# 606_outin_ichigojam.net
KiCad netlist of a schematic drawn in EAGLE
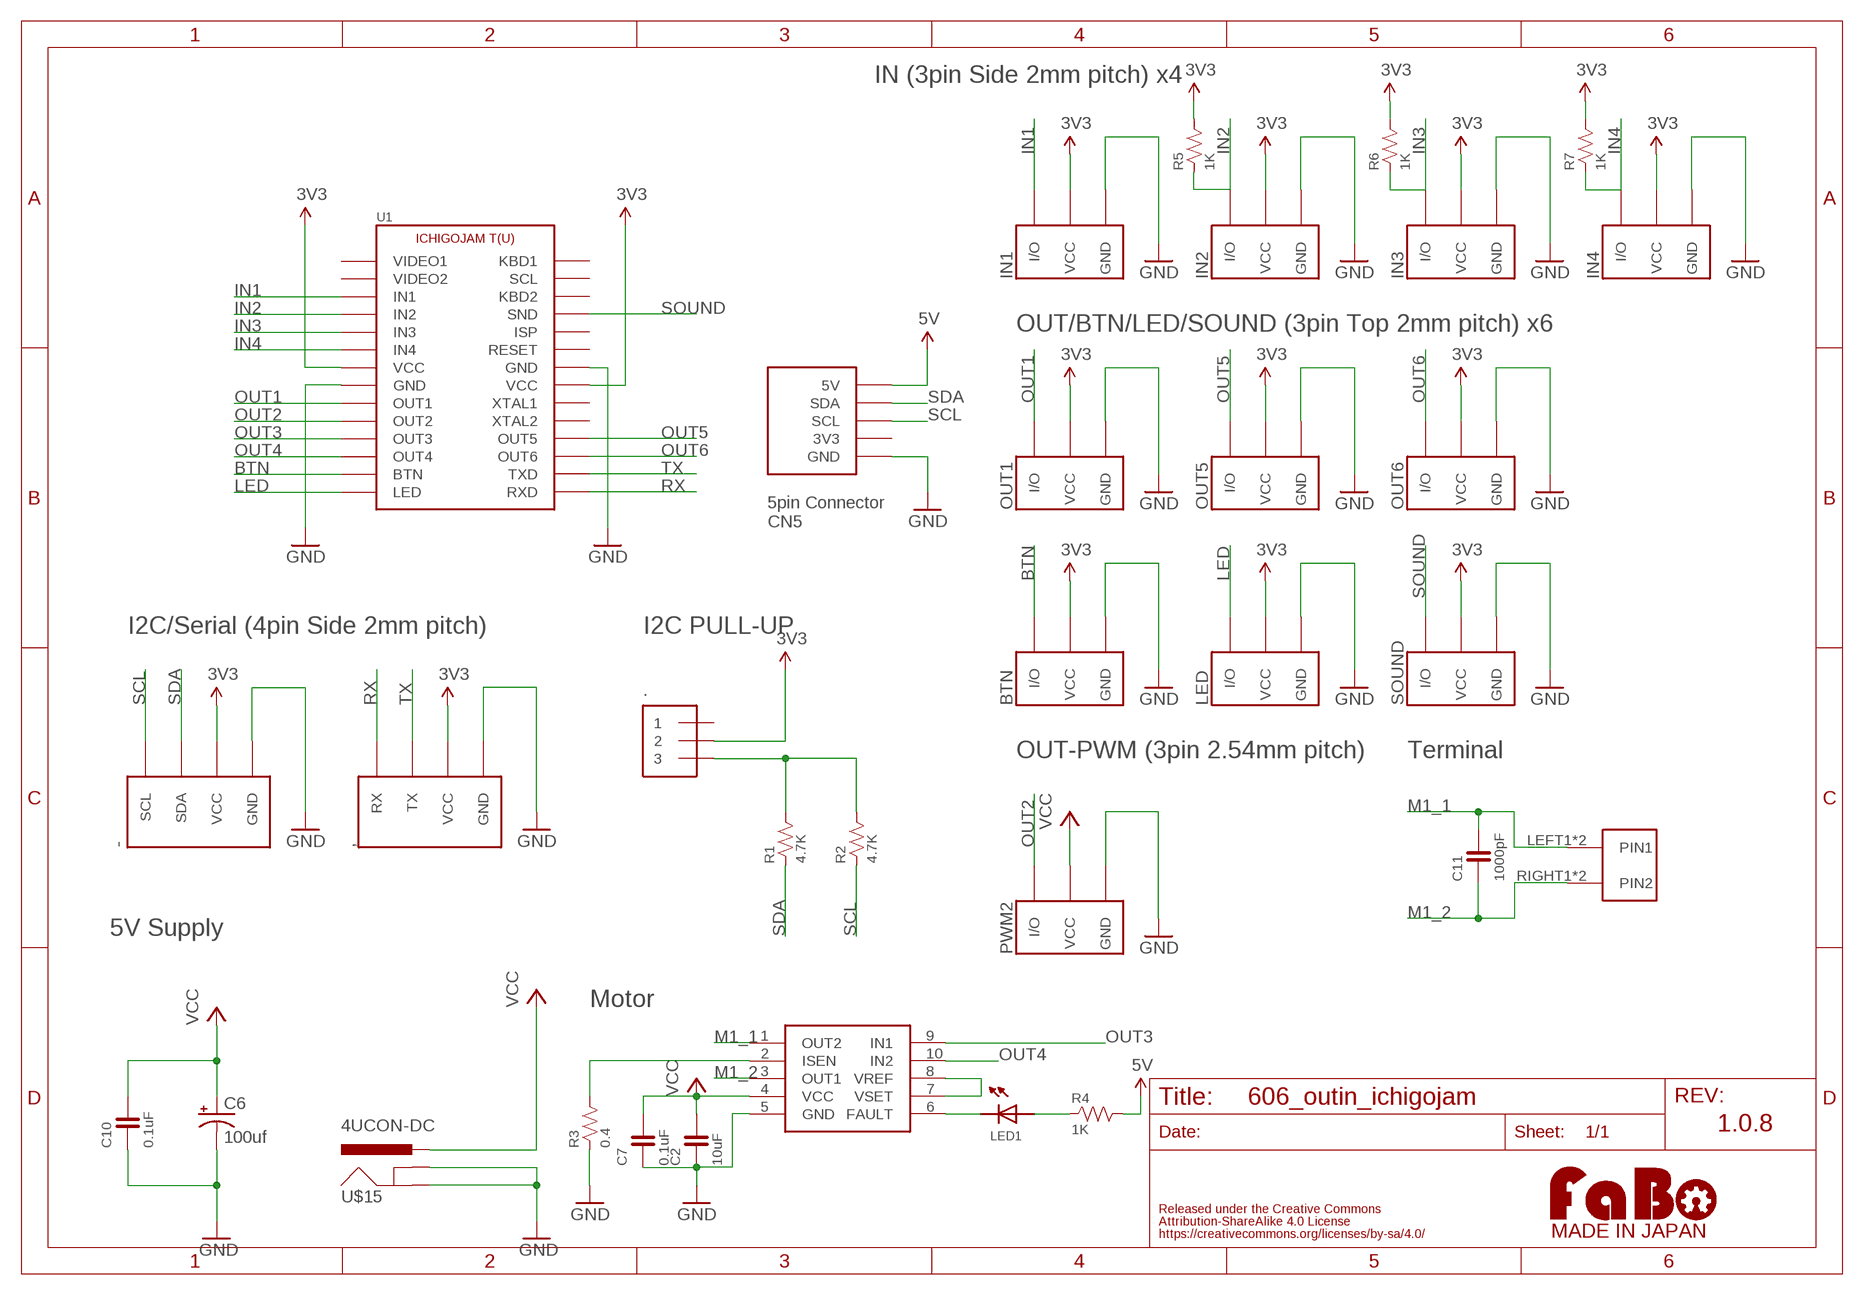
[diagram p0: schematic, sheet 1]

(export (version "E")
  (design (tool "Eeschema 10.0.6"))
  (components
    (comp (ref ",")
      (value "FABO_BRICK_SERIAL-S04B-PASK-2_LONG")
      (footprint "eagle-import:FABO_BRICK_SERIAL_S04B-PASK-2_LONG")
      (libsource (lib "eagle-import") (part "FABO_BRICK_SERIAL-S04B-PASK-2_LONG"))
    )
    (comp (ref "-")
      (value "FABO_BRICK_I2C-S04B-PASK-2_LONG")
      (footprint "eagle-import:FABO_BRICK_I2C_S04B-PASK-2_LONG")
      (libsource (lib "eagle-import") (part "FABO_BRICK_I2C-S04B-PASK-2_LONG"))
    )
    (comp (ref ".")
      (value "PIN_HEADER_1X3")
      (footprint "eagle-import:PIN_1X3")
      (libsource (lib "eagle-import") (part "PIN_HEADER_1X3"))
    )
    (comp (ref "BTN")
      (value "FABO_BRICK_3PIN-B03B-PASK-1")
      (footprint "eagle-import:FABO_BRICK_3PIN_B03B-PASK-1")
      (libsource (lib "eagle-import") (part "FABO_BRICK_3PIN-B03B-PASK-1"))
    )
    (comp (ref "C2")
      (value "10uF")
      (footprint "eagle-import:0603")
      (libsource (lib "eagle-import") (part "CAPACITOR-0603"))
    )
    (comp (ref "C6")
      (value "100uf")
      (footprint "eagle-import:153CLV-0405")
      (libsource (lib "eagle-import") (part "CPOL-US153CLV-0405"))
    )
    (comp (ref "C7")
      (value "0.1uF")
      (footprint "eagle-import:0603")
      (libsource (lib "eagle-import") (part "CAPACITOR-0603"))
    )
    (comp (ref "C10")
      (value "0.1uF")
      (footprint "eagle-import:0603")
      (libsource (lib "eagle-import") (part "CAPACITOR-0603"))
    )
    (comp (ref "C11")
      (value "1000pF")
      (footprint "eagle-import:0603")
      (libsource (lib "eagle-import") (part "CAPACITOR-0603"))
    )
    (comp (ref "IN1")
      (value "FABO_BRICK_3PIN-B03B-PASK-1")
      (footprint "eagle-import:FABO_BRICK_3PIN_B03B-PASK-1")
      (libsource (lib "eagle-import") (part "FABO_BRICK_3PIN-B03B-PASK-1"))
    )
    (comp (ref "IN2")
      (value "FABO_BRICK_3PIN-B03B-PASK-1")
      (footprint "eagle-import:FABO_BRICK_3PIN_B03B-PASK-1")
      (libsource (lib "eagle-import") (part "FABO_BRICK_3PIN-B03B-PASK-1"))
    )
    (comp (ref "IN3")
      (value "FABO_BRICK_3PIN-B03B-PASK-1")
      (footprint "eagle-import:FABO_BRICK_3PIN_B03B-PASK-1")
      (libsource (lib "eagle-import") (part "FABO_BRICK_3PIN-B03B-PASK-1"))
    )
    (comp (ref "IN4")
      (value "FABO_BRICK_3PIN-B03B-PASK-1")
      (footprint "eagle-import:FABO_BRICK_3PIN_B03B-PASK-1")
      (libsource (lib "eagle-import") (part "FABO_BRICK_3PIN-B03B-PASK-1"))
    )
    (comp (ref "LED")
      (value "FABO_BRICK_3PIN-B03B-PASK-1")
      (footprint "eagle-import:FABO_BRICK_3PIN_B03B-PASK-1")
      (libsource (lib "eagle-import") (part "FABO_BRICK_3PIN-B03B-PASK-1"))
    )
    (comp (ref "LED1")
      (value "LED-0603")
      (footprint "eagle-import:0603")
      (libsource (lib "eagle-import") (part "LED-0603"))
    )
    (comp (ref "OUT1")
      (value "FABO_BRICK_3PIN-B03B-PASK-1")
      (footprint "eagle-import:FABO_BRICK_3PIN_B03B-PASK-1")
      (libsource (lib "eagle-import") (part "FABO_BRICK_3PIN-B03B-PASK-1"))
    )
    (comp (ref "OUT5")
      (value "FABO_BRICK_3PIN-B03B-PASK-1")
      (footprint "eagle-import:FABO_BRICK_3PIN_B03B-PASK-1")
      (libsource (lib "eagle-import") (part "FABO_BRICK_3PIN-B03B-PASK-1"))
    )
    (comp (ref "OUT6")
      (value "FABO_BRICK_3PIN-B03B-PASK-1")
      (footprint "eagle-import:FABO_BRICK_3PIN_B03B-PASK-1")
      (libsource (lib "eagle-import") (part "FABO_BRICK_3PIN-B03B-PASK-1"))
    )
    (comp (ref "PWM2")
      (value "FABO_BRICK_3PIN-HEADER")
      (footprint "eagle-import:FABO_BRICK_3PIN_HEADER")
      (libsource (lib "eagle-import") (part "FABO_BRICK_3PIN-HEADER"))
    )
    (comp (ref "R1")
      (value "4.7K")
      (footprint "eagle-import:0603")
      (libsource (lib "eagle-import") (part "RESISTOR-0603"))
    )
    (comp (ref "R2")
      (value "4.7K")
      (footprint "eagle-import:0603")
      (libsource (lib "eagle-import") (part "RESISTOR-0603"))
    )
    (comp (ref "R3")
      (value "0.4")
      (footprint "eagle-import:0603")
      (libsource (lib "eagle-import") (part "RESISTOR-0603"))
    )
    (comp (ref "R4")
      (value "1K")
      (footprint "eagle-import:0603")
      (libsource (lib "eagle-import") (part "RESISTOR-0603"))
    )
    (comp (ref "R5")
      (value "1K")
      (footprint "eagle-import:0603")
      (libsource (lib "eagle-import") (part "RESISTOR-0603"))
    )
    (comp (ref "R6")
      (value "1K")
      (footprint "eagle-import:0603")
      (libsource (lib "eagle-import") (part "RESISTOR-0603"))
    )
    (comp (ref "R7")
      (value "1K")
      (footprint "eagle-import:0603")
      (libsource (lib "eagle-import") (part "RESISTOR-0603"))
    )
    (comp (ref "SOUND")
      (value "FABO_BRICK_3PIN-B03B-PASK-1")
      (footprint "eagle-import:FABO_BRICK_3PIN_B03B-PASK-1")
      (libsource (lib "eagle-import") (part "FABO_BRICK_3PIN-B03B-PASK-1"))
    )
    (comp (ref "U$3")
      (value "LOGO_FABO-M")
      (footprint "eagle-import:LOGO_FABO_MS")
      (libsource (lib "eagle-import") (part "LOGO_FABO-M"))
    )
    (comp (ref "U$6")
      (value "DRV8832")
      (footprint "eagle-import:DRV8830")
      (libsource (lib "eagle-import") (part "DRV8832"))
    )
    (comp (ref "U$12")
      (value "ML-1400-S1")
      (footprint "eagle-import:ML-1400-S1")
      (libsource (lib "eagle-import") (part "ML-1400-S1"))
    )
    (comp (ref "U$15")
      (value "4UCON-DC")
      (footprint "eagle-import:4UCON-DC")
      (libsource (lib "eagle-import") (part "4UCON-DC"))
    )
    (comp (ref "U1")
      (value "ICHIGOJAM_T-NOLABEL")
      (footprint "eagle-import:ICHIGOJAM_T_NOLABEL")
      (libsource (lib "eagle-import") (part "ICHIGOJAM_T-NOLABEL"))
    )
  )
  (nets
    (net (code "1") (name "/BTN") (class "Default")
      (node (ref "BTN") (pin "I/O") (pinfunction "I/O_I/O") (pintype "bidirectional"))
      (node (ref "U1") (pin "BTN") (pinfunction "BTN_BTN") (pintype "bidirectional"))
    )
    (net (code "2") (name "/IN1") (class "Default")
      (node (ref "IN1") (pin "I/O") (pinfunction "I/O_I/O") (pintype "bidirectional"))
      (node (ref "U1") (pin "IN1") (pinfunction "IN1_IN1") (pintype "bidirectional"))
    )
    (net (code "3") (name "/IN2") (class "Default")
      (node (ref "IN2") (pin "I/O") (pinfunction "I/O_I/O") (pintype "bidirectional"))
      (node (ref "R5") (pin "1") (pinfunction "1_1") (pintype "bidirectional"))
      (node (ref "U1") (pin "IN2") (pinfunction "IN2_IN2") (pintype "bidirectional"))
    )
    (net (code "4") (name "/IN3") (class "Default")
      (node (ref "IN3") (pin "I/O") (pinfunction "I/O_I/O") (pintype "bidirectional"))
      (node (ref "R6") (pin "1") (pinfunction "1_1") (pintype "bidirectional"))
      (node (ref "U1") (pin "IN3") (pinfunction "IN3_IN3") (pintype "bidirectional"))
    )
    (net (code "5") (name "/IN4") (class "Default")
      (node (ref "IN4") (pin "I/O") (pinfunction "I/O_I/O") (pintype "bidirectional"))
      (node (ref "R7") (pin "1") (pinfunction "1_1") (pintype "bidirectional"))
      (node (ref "U1") (pin "IN4") (pinfunction "IN4_IN4") (pintype "bidirectional"))
    )
    (net (code "6") (name "/LED") (class "Default")
      (node (ref "LED") (pin "I/O") (pinfunction "I/O_I/O") (pintype "bidirectional"))
      (node (ref "U1") (pin "LED") (pinfunction "LED_LED") (pintype "bidirectional"))
    )
    (net (code "7") (name "/M1_1") (class "Default")
      (node (ref "C11") (pin "2") (pinfunction "2_2") (pintype "passive"))
      (node (ref "U$12") (pin "LEFT1") (pinfunction "PIN1_LEFT1") (pintype "bidirectional"))
      (node (ref "U$12") (pin "LEFT2") (pinfunction "PIN1_LEFT2") (pintype "bidirectional"))
      (node (ref "U$6") (pin "1") (pinfunction "OUT2_1") (pintype "bidirectional"))
    )
    (net (code "8") (name "/M1_2") (class "Default")
      (node (ref "C11") (pin "1") (pinfunction "1_1") (pintype "passive"))
      (node (ref "U$12") (pin "RIGHT1") (pinfunction "PIN2_RIGHT1") (pintype "bidirectional"))
      (node (ref "U$12") (pin "RIGHT2") (pinfunction "PIN2_RIGHT2") (pintype "bidirectional"))
      (node (ref "U$6") (pin "3") (pinfunction "OUT1_3") (pintype "bidirectional"))
    )
    (net (code "9") (name "/OUT1") (class "Default")
      (node (ref "OUT1") (pin "I/O") (pinfunction "I/O_I/O") (pintype "bidirectional"))
      (node (ref "U1") (pin "OUT1") (pinfunction "OUT1_OUT1") (pintype "bidirectional"))
    )
    (net (code "10") (name "/OUT2") (class "Default")
      (node (ref "PWM2") (pin "I/O") (pinfunction "I/O_I/O") (pintype "bidirectional"))
      (node (ref "U1") (pin "OUT2") (pinfunction "OUT2_OUT2") (pintype "bidirectional"))
    )
    (net (code "11") (name "/OUT3") (class "Default")
      (node (ref "U$6") (pin "9") (pinfunction "IN1_9") (pintype "bidirectional"))
      (node (ref "U1") (pin "OUT3") (pinfunction "OUT3_OUT3") (pintype "bidirectional"))
    )
    (net (code "12") (name "/OUT4") (class "Default")
      (node (ref "U$6") (pin "10") (pinfunction "IN2_10") (pintype "bidirectional"))
      (node (ref "U1") (pin "OUT4") (pinfunction "OUT4_OUT4") (pintype "bidirectional"))
    )
    (net (code "13") (name "/OUT5") (class "Default")
      (node (ref "OUT5") (pin "I/O") (pinfunction "I/O_I/O") (pintype "bidirectional"))
      (node (ref "U1") (pin "OUT5") (pinfunction "OUT5_OUT5") (pintype "bidirectional"))
    )
    (net (code "14") (name "/OUT6") (class "Default")
      (node (ref "OUT6") (pin "I/O") (pinfunction "I/O_I/O") (pintype "bidirectional"))
      (node (ref "U1") (pin "OUT6") (pinfunction "OUT6_OUT6") (pintype "bidirectional"))
    )
    (net (code "15") (name "/RX") (class "Default")
      (node (ref ",") (pin "RX") (pinfunction "RX_RX") (pintype "bidirectional"))
      (node (ref "U1") (pin "RXD") (pinfunction "RXD_RXD") (pintype "bidirectional"))
    )
    (net (code "16") (name "/SCL") (class "Default")
      (node (ref "-") (pin "SCL") (pinfunction "SCL_SCL") (pintype "bidirectional"))
      (node (ref "R2") (pin "1") (pinfunction "1_1") (pintype "bidirectional"))
      (node (ref "U1") (pin "SCL2") (pinfunction "SCL_SCL2") (pintype "bidirectional"))
    )
    (net (code "17") (name "/SDA") (class "Default")
      (node (ref "-") (pin "SDA") (pinfunction "SDA_SDA") (pintype "bidirectional"))
      (node (ref "R1") (pin "1") (pinfunction "1_1") (pintype "bidirectional"))
      (node (ref "U1") (pin "SDA") (pinfunction "SDA_SDA") (pintype "bidirectional"))
    )
    (net (code "18") (name "/SOUND") (class "Default")
      (node (ref "SOUND") (pin "I/O") (pinfunction "I/O_I/O") (pintype "bidirectional"))
      (node (ref "U1") (pin "SND") (pinfunction "SND_SND") (pintype "bidirectional"))
    )
    (net (code "19") (name "/TX") (class "Default")
      (node (ref ",") (pin "TX") (pinfunction "TX_TX") (pintype "bidirectional"))
      (node (ref "U1") (pin "TXD") (pinfunction "TXD_TXD") (pintype "bidirectional"))
    )
    (net (code "20") (name "3V3") (class "Default")
      (node (ref ",") (pin "VCC") (pinfunction "VCC_VCC") (pintype "bidirectional"))
      (node (ref "-") (pin "VCC") (pinfunction "VCC_VCC") (pintype "bidirectional"))
      (node (ref ".") (pin "2") (pinfunction "2_2") (pintype "bidirectional"))
      (node (ref "BTN") (pin "VCC") (pinfunction "VCC_VCC") (pintype "bidirectional"))
      (node (ref "IN1") (pin "VCC") (pinfunction "VCC_VCC") (pintype "bidirectional"))
      (node (ref "IN2") (pin "VCC") (pinfunction "VCC_VCC") (pintype "bidirectional"))
      (node (ref "IN3") (pin "VCC") (pinfunction "VCC_VCC") (pintype "bidirectional"))
      (node (ref "IN4") (pin "VCC") (pinfunction "VCC_VCC") (pintype "bidirectional"))
      (node (ref "LED") (pin "VCC") (pinfunction "VCC_VCC") (pintype "bidirectional"))
      (node (ref "OUT1") (pin "VCC") (pinfunction "VCC_VCC") (pintype "bidirectional"))
      (node (ref "OUT5") (pin "VCC") (pinfunction "VCC_VCC") (pintype "bidirectional"))
      (node (ref "OUT6") (pin "VCC") (pinfunction "VCC_VCC") (pintype "bidirectional"))
      (node (ref "R5") (pin "2") (pinfunction "2_2") (pintype "bidirectional"))
      (node (ref "R6") (pin "2") (pinfunction "2_2") (pintype "bidirectional"))
      (node (ref "R7") (pin "2") (pinfunction "2_2") (pintype "bidirectional"))
      (node (ref "SOUND") (pin "VCC") (pinfunction "VCC_VCC") (pintype "bidirectional"))
      (node (ref "U1") (pin "VCC1") (pinfunction "VCC_VCC1") (pintype "bidirectional"))
      (node (ref "U1") (pin "VCC2") (pinfunction "VCC_VCC2") (pintype "bidirectional"))
    )
    (net (code "21") (name "5V") (class "Default")
      (node (ref "R4") (pin "2") (pinfunction "2_2") (pintype "bidirectional"))
      (node (ref "U1") (pin "5V") (pinfunction "5V_5V") (pintype "bidirectional"))
    )
    (net (code "22") (name "GND") (class "Default")
      (node (ref ",") (pin "GND") (pinfunction "GND_GND") (pintype "bidirectional"))
      (node (ref "-") (pin "GND") (pinfunction "GND_GND") (pintype "bidirectional"))
      (node (ref "BTN") (pin "GND") (pinfunction "GND_GND") (pintype "bidirectional"))
      (node (ref "C10") (pin "1") (pinfunction "1_1") (pintype "passive"))
      (node (ref "C2") (pin "1") (pinfunction "1_1") (pintype "passive"))
      (node (ref "C6") (pin "-") (pinfunction "-_-") (pintype "passive"))
      (node (ref "C7") (pin "1") (pinfunction "1_1") (pintype "passive"))
      (node (ref "IN1") (pin "GND") (pinfunction "GND_GND") (pintype "bidirectional"))
      (node (ref "IN2") (pin "GND") (pinfunction "GND_GND") (pintype "bidirectional"))
      (node (ref "IN3") (pin "GND") (pinfunction "GND_GND") (pintype "bidirectional"))
      (node (ref "IN4") (pin "GND") (pinfunction "GND_GND") (pintype "bidirectional"))
      (node (ref "LED") (pin "GND") (pinfunction "GND_GND") (pintype "bidirectional"))
      (node (ref "OUT1") (pin "GND") (pinfunction "GND_GND") (pintype "bidirectional"))
      (node (ref "OUT5") (pin "GND") (pinfunction "GND_GND") (pintype "bidirectional"))
      (node (ref "OUT6") (pin "GND") (pinfunction "GND_GND") (pintype "bidirectional"))
      (node (ref "PWM2") (pin "GND") (pinfunction "GND_GND") (pintype "bidirectional"))
      (node (ref "R3") (pin "1") (pinfunction "1_1") (pintype "bidirectional"))
      (node (ref "SOUND") (pin "GND") (pinfunction "GND_GND") (pintype "bidirectional"))
      (node (ref "U$15") (pin "GND1") (pinfunction "GND_GND1") (pintype "bidirectional"))
      (node (ref "U$15") (pin "GND2") (pinfunction "GNDBREAK_GND2") (pintype "bidirectional"))
      (node (ref "U$6") (pin "5") (pinfunction "GND_5") (pintype "bidirectional"))
      (node (ref "U1") (pin "GND1") (pinfunction "GND_GND1") (pintype "bidirectional"))
      (node (ref "U1") (pin "GND2") (pinfunction "GND_GND2") (pintype "bidirectional"))
      (node (ref "U1") (pin "GND3") (pinfunction "GND_GND3") (pintype "bidirectional"))
    )
    (net (code "23") (name "Net-(.-Pad3)") (class "Default")
      (node (ref ".") (pin "3") (pinfunction "3_3") (pintype "bidirectional"))
      (node (ref "R1") (pin "2") (pinfunction "2_2") (pintype "bidirectional"))
      (node (ref "R2") (pin "2") (pinfunction "2_2") (pintype "bidirectional"))
    )
    (net (code "24") (name "Net-(LED1-PadANODE)") (class "Default")
      (node (ref "LED1") (pin "ANODE") (pinfunction "ANODE_ANODE") (pintype "passive"))
      (node (ref "R4") (pin "1") (pinfunction "1_1") (pintype "bidirectional"))
    )
    (net (code "25") (name "Net-(U$6-FAULT)") (class "Default")
      (node (ref "LED1") (pin "CATHODE") (pinfunction "CATHODE_CATHODE") (pintype "passive"))
      (node (ref "U$6") (pin "6") (pinfunction "FAULT_6") (pintype "bidirectional"))
    )
    (net (code "26") (name "Net-(U$6-ISEN)") (class "Default")
      (node (ref "R3") (pin "2") (pinfunction "2_2") (pintype "bidirectional"))
      (node (ref "U$6") (pin "2") (pinfunction "ISEN_2") (pintype "bidirectional"))
    )
    (net (code "27") (name "Net-(U$6-VREF)") (class "Default")
      (node (ref "U$6") (pin "7") (pinfunction "VSET_7") (pintype "bidirectional"))
      (node (ref "U$6") (pin "8") (pinfunction "VREF_8") (pintype "bidirectional"))
    )
    (net (code "28") (name "VCC") (class "Default")
      (node (ref "C10") (pin "2") (pinfunction "2_2") (pintype "passive"))
      (node (ref "C2") (pin "2") (pinfunction "2_2") (pintype "passive"))
      (node (ref "C6") (pin "+") (pinfunction "+_+") (pintype "passive"))
      (node (ref "C7") (pin "2") (pinfunction "2_2") (pintype "passive"))
      (node (ref "PWM2") (pin "VCC") (pinfunction "VCC_VCC") (pintype "bidirectional"))
      (node (ref "U$15") (pin "VCC") (pinfunction "PWR_VCC") (pintype "bidirectional"))
      (node (ref "U$6") (pin "4") (pinfunction "VCC_4") (pintype "bidirectional"))
    )
    (net (code "29") (name "unconnected-(.-Pad1)") (class "Default")
      (node (ref ".") (pin "1") (pinfunction "1_1") (pintype "bidirectional"))
    )
    (net (code "30") (name "unconnected-(U1-Pad3V3)") (class "Default")
      (node (ref "U1") (pin "3V3") (pinfunction "3V3_3V3") (pintype "bidirectional"))
    )
    (net (code "31") (name "unconnected-(U1-PadISP)") (class "Default")
      (node (ref "U1") (pin "ISP") (pinfunction "ISP_ISP") (pintype "bidirectional"))
    )
    (net (code "32") (name "unconnected-(U1-PadKBD1)") (class "Default")
      (node (ref "U1") (pin "KBD1") (pinfunction "KBD1_KBD1") (pintype "bidirectional"))
    )
    (net (code "33") (name "unconnected-(U1-PadKBD2)") (class "Default")
      (node (ref "U1") (pin "KBD2") (pinfunction "KBD2_KBD2") (pintype "bidirectional"))
    )
    (net (code "34") (name "unconnected-(U1-PadVIDEO1)") (class "Default")
      (node (ref "U1") (pin "VIDEO1") (pinfunction "VIDEO1_VIDEO1") (pintype "bidirectional"))
    )
    (net (code "35") (name "unconnected-(U1-PadVIDEO2)") (class "Default")
      (node (ref "U1") (pin "VIDEO2") (pinfunction "VIDEO2_VIDEO2") (pintype "bidirectional"))
    )
    (net (code "36") (name "unconnected-(U1-PadXTAL1)") (class "Default")
      (node (ref "U1") (pin "XTAL1") (pinfunction "XTAL1_XTAL1") (pintype "bidirectional"))
    )
    (net (code "37") (name "unconnected-(U1-PadXTAL2)") (class "Default")
      (node (ref "U1") (pin "XTAL2") (pinfunction "XTAL2_XTAL2") (pintype "bidirectional"))
    )
    (net (code "38") (name "unconnected-(U1-RESET-PadRST)") (class "Default")
      (node (ref "U1") (pin "RST") (pinfunction "RESET_RST") (pintype "bidirectional"))
    )
    (net (code "39") (name "unconnected-(U1-SCL-PadSCL1)") (class "Default")
      (node (ref "U1") (pin "SCL1") (pinfunction "SCL_SCL1") (pintype "bidirectional"))
    )
  )
)
